# MS5803-01_BA.net
KiCad netlist of a schematic drawn in Altium Designer
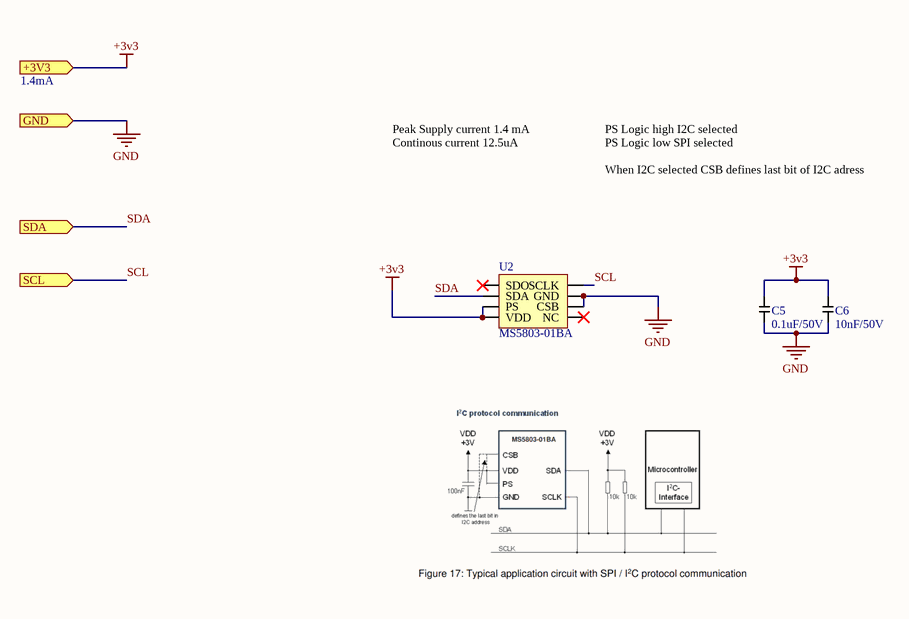
[diagram p0: MS5803-01.BA.SchDoc]

(export (version "E")
  (design (tool "Eeschema 10.0.6"))
  (components
    (comp (ref "C5")
      (value "0.1uF/50V")
      (footprint "Cap_0805")
      (description "MLCC (2012) 0805 100nF 50VDC ±5% X7R")
      (libsource (lib "Roket_Library") (part "CL21B104JBCNNNC"))
    )
    (comp (ref "C6")
      (value "10nF/50V")
      (footprint "Cap_0805")
      (description "MLCC (2012) 0805 10nF 50VDC ±10% X7R")
      (libsource (lib "Roket_Library") (part "CL21B103KBANNNC"))
    )
    (comp (ref "U2")
      (value "MS5803-01BA")
      (footprint "MS5803-01BA")
      (description "Pressure Sensor 0.15PSI ~ 18.85PSI (1kPa ~ 130kPa) Absolute 24 b 8-SMD Module")
      (libsource (lib "Roket_Library") (part "MS5803-01BA"))
    )
  )
  (nets
    (net (code "1") (name "+3v3") (class "Default")
      (node (ref "C5") (pin "1") (pinfunction "1_1") (pintype "passive"))
      (node (ref "C6") (pin "2") (pinfunction "2_2") (pintype "passive"))
      (node (ref "U2") (pin "5") (pinfunction "VDD_5") (pintype "passive"))
      (node (ref "U2") (pin "6") (pinfunction "PS_6") (pintype "passive"))
    )
    (net (code "2") (name "/SCL") (class "Default")
      (node (ref "U2") (pin "1") (pinfunction "SCLK_1") (pintype "passive"))
    )
    (net (code "3") (name "/SDA") (class "Default")
      (node (ref "U2") (pin "7") (pinfunction "SDA_7") (pintype "passive"))
    )
    (net (code "4") (name "GND") (class "Default")
      (node (ref "C5") (pin "2") (pinfunction "2_2") (pintype "passive"))
      (node (ref "C6") (pin "1") (pinfunction "1_1") (pintype "passive"))
      (node (ref "U2") (pin "2") (pinfunction "GND_2") (pintype "passive"))
      (node (ref "U2") (pin "3") (pinfunction "CSB_3") (pintype "passive"))
    )
    (net (code "5") (name "unconnected-(U2-NC-Pad4)") (class "Default")
      (node (ref "U2") (pin "4") (pinfunction "NC_4") (pintype "passive+no_connect"))
    )
    (net (code "6") (name "unconnected-(U2-SDO-Pad8)") (class "Default")
      (node (ref "U2") (pin "8") (pinfunction "SDO_8") (pintype "passive+no_connect"))
    )
  )
)
